# NANO103.net
KiCad netlist of a schematic drawn in Altium Designer
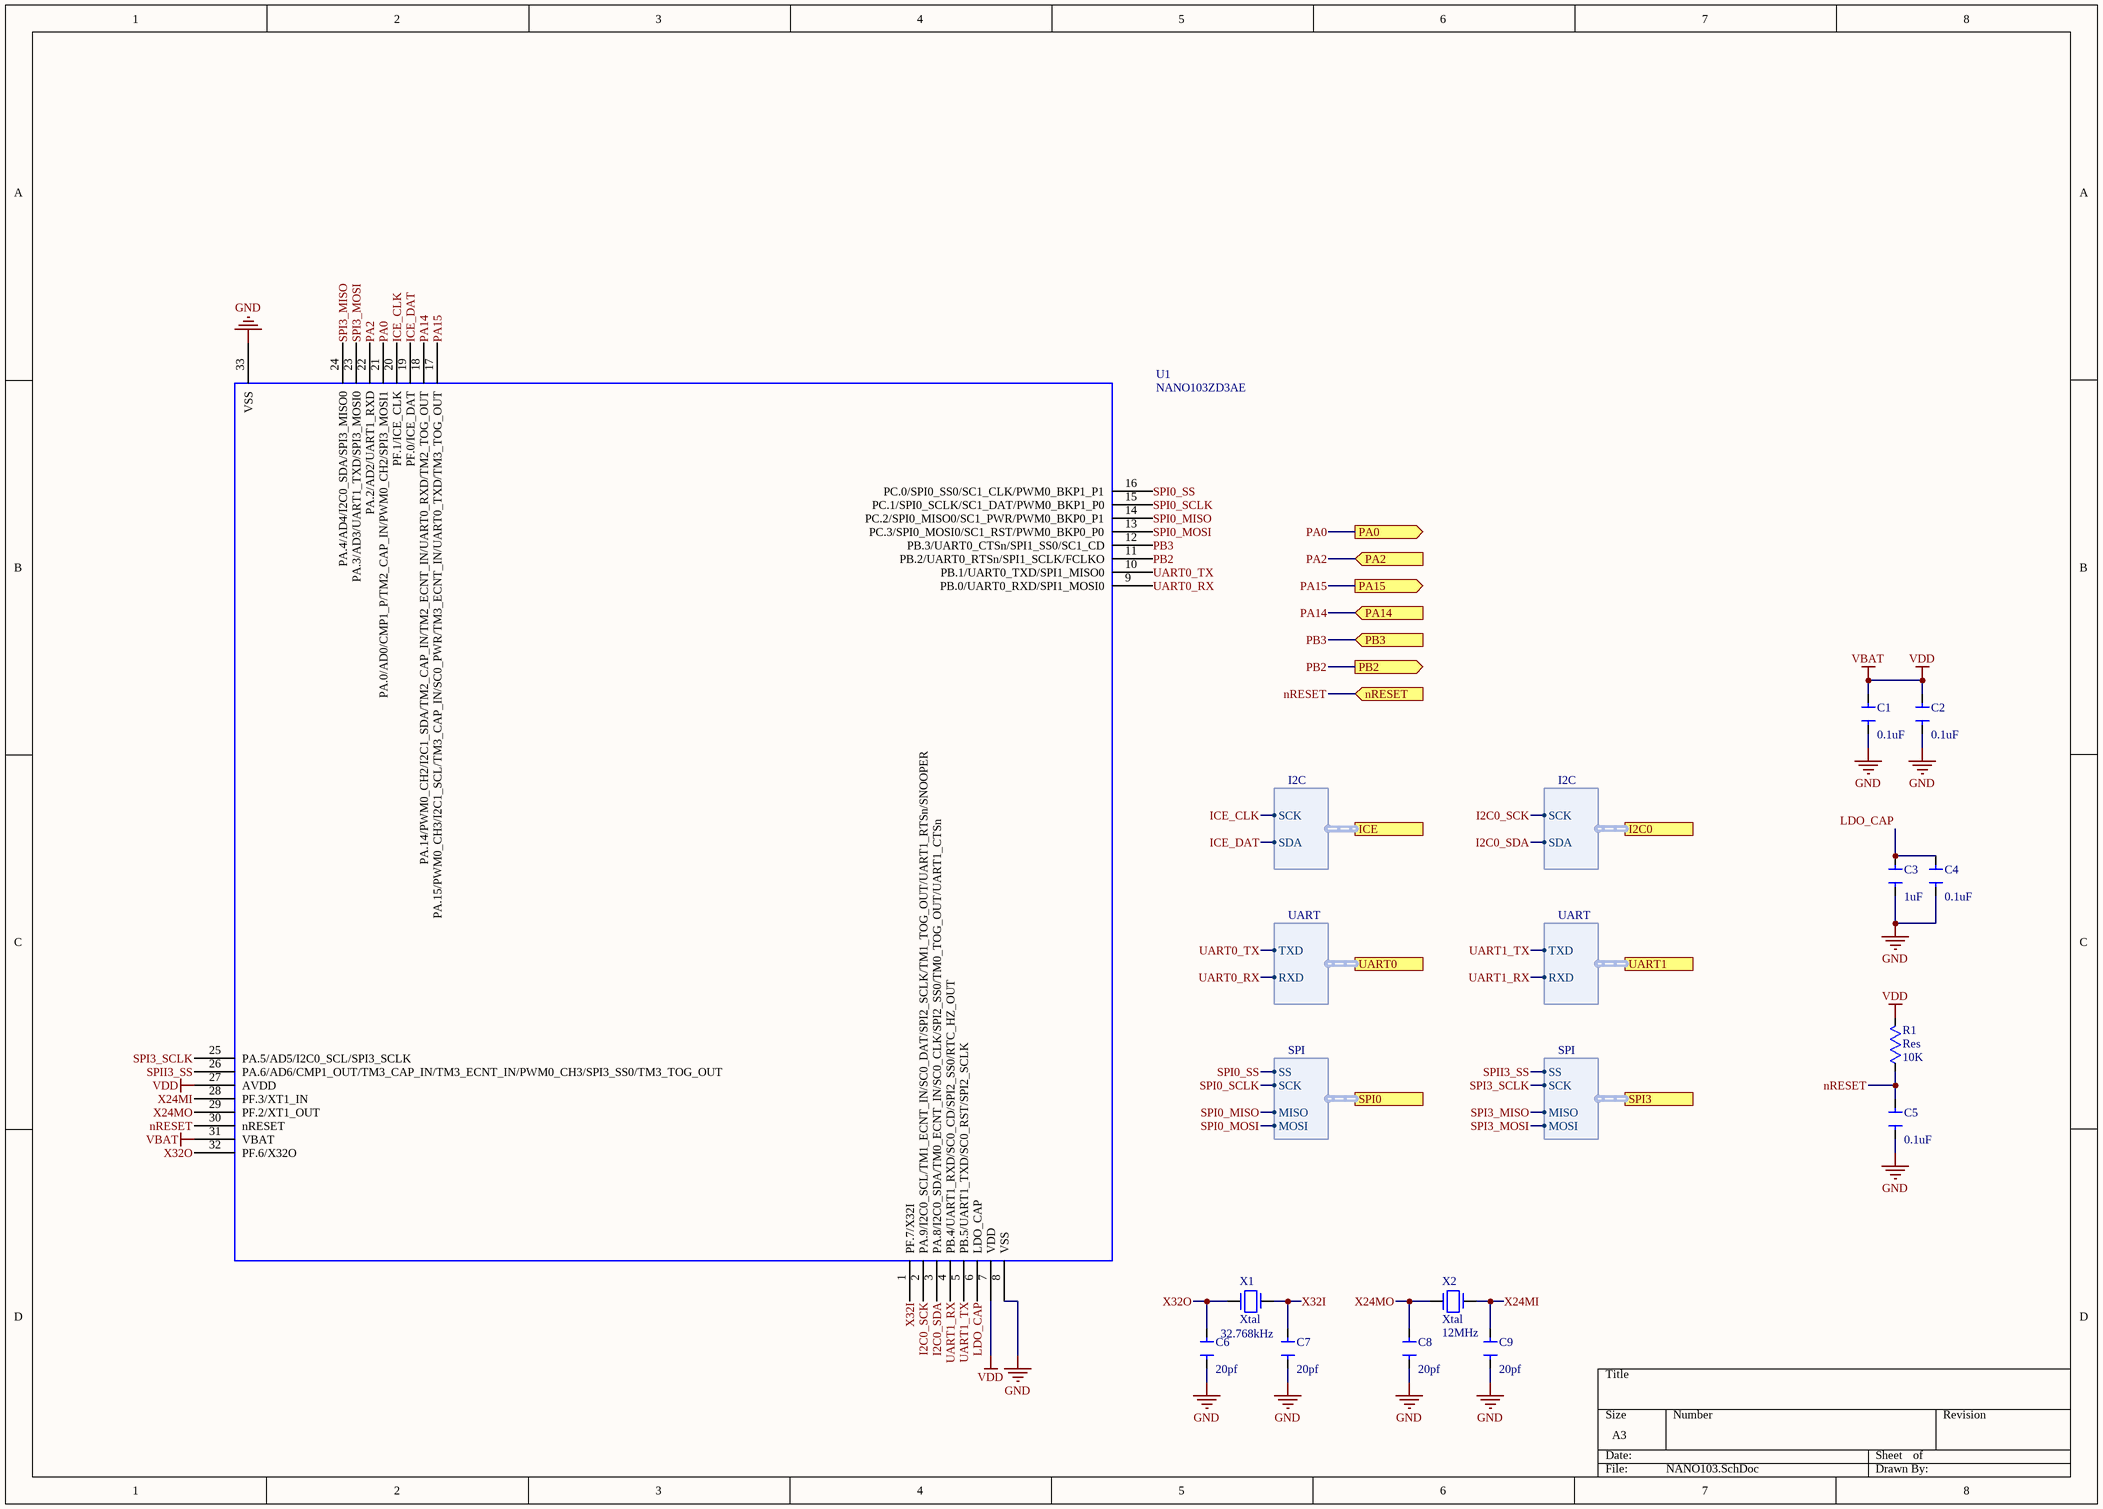
[diagram p0: NANO103.SchDoc]

(export (version "E")
  (design (tool "Eeschema 10.0.6"))
  (components
    (comp (ref "C1")
      (value "0.1uF")
      (footprint "Cap_0603")
      (fields (field (name "Comment") "Cap"))
      (libsource (lib "ZGR") (part "Cap"))
    )
    (comp (ref "C2")
      (value "0.1uF")
      (footprint "Cap_0603")
      (fields (field (name "Comment") "Cap"))
      (libsource (lib "ZGR") (part "Cap"))
    )
    (comp (ref "C3")
      (value "1uF")
      (footprint "Cap_0603")
      (fields (field (name "Comment") "Cap"))
      (libsource (lib "ZGR") (part "Cap"))
    )
    (comp (ref "C4")
      (value "0.1uF")
      (footprint "Cap_0603")
      (fields (field (name "Comment") "Cap"))
      (libsource (lib "ZGR") (part "Cap"))
    )
    (comp (ref "C5")
      (value "0.1uF")
      (footprint "Cap_0603")
      (fields (field (name "Comment") "Cap"))
      (libsource (lib "ZGR") (part "Cap"))
    )
    (comp (ref "C6")
      (value "20pf")
      (footprint "Cap_0603")
      (fields (field (name "Comment") "Cap"))
      (libsource (lib "ZGR") (part "Cap"))
    )
    (comp (ref "C7")
      (value "20pf")
      (footprint "Cap_0603")
      (fields (field (name "Comment") "Cap"))
      (libsource (lib "ZGR") (part "Cap"))
    )
    (comp (ref "C8")
      (value "20pf")
      (footprint "Cap_0603")
      (fields (field (name "Comment") "Cap"))
      (libsource (lib "ZGR") (part "Cap"))
    )
    (comp (ref "C9")
      (value "20pf")
      (footprint "Cap_0603")
      (fields (field (name "Comment") "Cap"))
      (libsource (lib "ZGR") (part "Cap"))
    )
    (comp (ref "R1")
      (value "Res")
      (footprint "RES_0603")
      (fields (field (name "ALTIUM_VALUE") "10K"))
      (libsource (lib "ZGR") (part "Res"))
    )
    (comp (ref "U1")
      (value "NANO103ZD3AE")
      (footprint "MCU_QFN_33_5x5")
      (libsource (lib "NUVOTON") (part "NANO103ZD3AE"))
    )
    (comp (ref "X1")
      (value "Xtal")
      (footprint "X3215")
      (fields (field (name "ALTIUM_VALUE") "32.768kHz"))
      (libsource (lib "ZGR") (part "Xtal"))
    )
    (comp (ref "X2")
      (value "Xtal")
      (footprint "2520S")
      (fields (field (name "ALTIUM_VALUE") "12MHz"))
      (libsource (lib "ZGR") (part "Xtal"))
    )
  )
  (nets
    (net (code "4") (name "/I2C0_SCK") (class "Default")
      (node (ref "U1") (pin "2") (pinfunction "PA.9/I2C0_SCL/TM1_ECNT_IN/SC0_DAT/SPI2_SCLK/TM1_TOG_OUT/UART1_RTSn/SNOOPER_2") (pintype "passive"))
    )
    (net (code "5") (name "/I2C0_SDA") (class "Default")
      (node (ref "U1") (pin "3") (pinfunction "PA.8/I2C0_SDA/TM0_ECNT_IN/SC0_CLK/SPI2_SS0/TM0_TOG_OUT/UART1_CTSn_3") (pintype "passive"))
    )
    (net (code "6") (name "/ICE_CLK") (class "Default")
      (node (ref "U1") (pin "20") (pinfunction "PF.1/ICE_CLK_20") (pintype "passive"))
    )
    (net (code "7") (name "/ICE_DAT") (class "Default")
      (node (ref "U1") (pin "19") (pinfunction "PF.0/ICE_DAT_19") (pintype "passive"))
    )
    (net (code "8") (name "/LDO_CAP") (class "Default")
      (node (ref "C3") (pin "1") (pinfunction "1_1") (pintype "passive"))
      (node (ref "C4") (pin "1") (pinfunction "1_1") (pintype "passive"))
      (node (ref "U1") (pin "6") (pinfunction "LDO_CAP_6") (pintype "passive"))
    )
    (net (code "9") (name "/PA0") (class "Default")
      (node (ref "U1") (pin "21") (pinfunction "PA.0/AD0/CMP1_P/TM2_CAP_IN/PWM0_CH2/SPI3_MOSI1_21") (pintype "passive"))
    )
    (net (code "10") (name "/PA2") (class "Default")
      (node (ref "U1") (pin "22") (pinfunction "PA.2/AD2/UART1_RXD_22") (pintype "passive"))
    )
    (net (code "11") (name "/PA14") (class "Default")
      (node (ref "U1") (pin "18") (pinfunction "PA.14/PWM0_CH2/I2C1_SDA/TM2_CAP_IN/TM2_ECNT_IN/UART0_RXD/TM2_TOG_OUT_18") (pintype "passive"))
    )
    (net (code "12") (name "/PA15") (class "Default")
      (node (ref "U1") (pin "17") (pinfunction "PA.15/PWM0_CH3/I2C1_SCL/TM3_CAP_IN/SC0_PWR/TM3_ECNT_IN/UART0_TXD/TM3_TOG_OUT_17") (pintype "passive"))
    )
    (net (code "13") (name "/PB2") (class "Default")
      (node (ref "U1") (pin "11") (pinfunction "PB.2/UART0_RTSn/SPI1_SCLK/FCLKO_11") (pintype "passive"))
    )
    (net (code "14") (name "/PB3") (class "Default")
      (node (ref "U1") (pin "12") (pinfunction "PB.3/UART0_CTSn/SPI1_SS0/SC1_CD_12") (pintype "passive"))
    )
    (net (code "15") (name "/SPI0_MISO") (class "Default")
      (node (ref "U1") (pin "14") (pinfunction "PC.2/SPI0_MISO0/SC1_PWR/PWM0_BKP0_P1_14") (pintype "passive"))
    )
    (net (code "16") (name "/SPI0_MOSI") (class "Default")
      (node (ref "U1") (pin "13") (pinfunction "PC.3/SPI0_MOSI0/SC1_RST/PWM0_BKP0_P0_13") (pintype "passive"))
    )
    (net (code "17") (name "/SPI0_SCLK") (class "Default")
      (node (ref "U1") (pin "15") (pinfunction "PC.1/SPI0_SCLK/SC1_DAT/PWM0_BKP1_P0_15") (pintype "passive"))
    )
    (net (code "18") (name "/SPI0_SS") (class "Default")
      (node (ref "U1") (pin "16") (pinfunction "PC.0/SPI0_SS0/SC1_CLK/PWM0_BKP1_P1_16") (pintype "passive"))
    )
    (net (code "19") (name "/SPI3_MISO") (class "Default")
      (node (ref "U1") (pin "24") (pinfunction "PA.4/AD4/I2C0_SDA/SPI3_MISO0_24") (pintype "passive"))
    )
    (net (code "20") (name "/SPI3_MOSI") (class "Default")
      (node (ref "U1") (pin "23") (pinfunction "PA.3/AD3/UART1_TXD/SPI3_MOSI0_23") (pintype "passive"))
    )
    (net (code "21") (name "/SPI3_SCLK") (class "Default")
      (node (ref "U1") (pin "25") (pinfunction "PA.5/AD5/I2C0_SCL/SPI3_SCLK_25") (pintype "passive"))
    )
    (net (code "22") (name "/SPII3_SS") (class "Default")
      (node (ref "U1") (pin "26") (pinfunction "PA.6/AD6/CMP1_OUT/TM3_CAP_IN/TM3_ECNT_IN/PWM0_CH3/SPI3_SS0/TM3_TOG_OUT_26") (pintype "passive"))
    )
    (net (code "23") (name "/UART0_RX") (class "Default")
      (node (ref "U1") (pin "9") (pinfunction "PB.0/UART0_RXD/SPI1_MOSI0_9") (pintype "passive"))
    )
    (net (code "24") (name "/UART0_TX") (class "Default")
      (node (ref "U1") (pin "10") (pinfunction "PB.1/UART0_TXD/SPI1_MISO0_10") (pintype "passive"))
    )
    (net (code "25") (name "/UART1_RX") (class "Default")
      (node (ref "U1") (pin "4") (pinfunction "PB.4/UART1_RXD/SC0_CD/SPI2_SS0/RTC_HZ_OUT_4") (pintype "passive"))
    )
    (net (code "26") (name "/UART1_TX") (class "Default")
      (node (ref "U1") (pin "5") (pinfunction "PB.5/UART1_TXD/SC0_RST/SPI2_SCLK_5") (pintype "passive"))
    )
    (net (code "27") (name "/X24MI") (class "Default")
      (node (ref "C9") (pin "1") (pinfunction "1_1") (pintype "passive"))
      (node (ref "U1") (pin "28") (pinfunction "PF.3/XT1_IN_28") (pintype "passive"))
      (node (ref "X2") (pin "1") (pintype "passive"))
    )
    (net (code "28") (name "/X24MO") (class "Default")
      (node (ref "C8") (pin "1") (pinfunction "1_1") (pintype "passive"))
      (node (ref "U1") (pin "29") (pinfunction "PF.2/XT1_OUT_29") (pintype "passive"))
      (node (ref "X2") (pin "2") (pintype "passive"))
    )
    (net (code "29") (name "/X32I") (class "Default")
      (node (ref "C7") (pin "1") (pinfunction "1_1") (pintype "passive"))
      (node (ref "U1") (pin "1") (pinfunction "PF.7/X32I_1") (pintype "passive"))
      (node (ref "X1") (pin "1") (pintype "passive"))
    )
    (net (code "30") (name "/X32O") (class "Default")
      (node (ref "C6") (pin "1") (pinfunction "1_1") (pintype "passive"))
      (node (ref "U1") (pin "32") (pinfunction "PF.6/X32O_32") (pintype "passive"))
      (node (ref "X1") (pin "2") (pintype "passive"))
    )
    (net (code "31") (name "/nRESET") (class "Default")
      (node (ref "C5") (pin "1") (pinfunction "1_1") (pintype "passive"))
      (node (ref "R1") (pin "2") (pinfunction "2_2") (pintype "passive"))
      (node (ref "U1") (pin "30") (pinfunction "nRESET_30") (pintype "passive"))
    )
    (net (code "35") (name "GND") (class "Default")
      (node (ref "C1") (pin "2") (pinfunction "2_2") (pintype "passive"))
      (node (ref "C2") (pin "2") (pinfunction "2_2") (pintype "passive"))
      (node (ref "C3") (pin "2") (pinfunction "2_2") (pintype "passive"))
      (node (ref "C4") (pin "2") (pinfunction "2_2") (pintype "passive"))
      (node (ref "C5") (pin "2") (pinfunction "2_2") (pintype "passive"))
      (node (ref "C6") (pin "2") (pinfunction "2_2") (pintype "passive"))
      (node (ref "C7") (pin "2") (pinfunction "2_2") (pintype "passive"))
      (node (ref "C8") (pin "2") (pinfunction "2_2") (pintype "passive"))
      (node (ref "C9") (pin "2") (pinfunction "2_2") (pintype "passive"))
      (node (ref "U1") (pin "33") (pinfunction "VSS_33") (pintype "passive"))
      (node (ref "U1") (pin "8") (pinfunction "VSS_8") (pintype "passive"))
    )
    (net (code "36") (name "VBAT") (class "Default")
      (node (ref "C1") (pin "1") (pinfunction "1_1") (pintype "passive"))
      (node (ref "C2") (pin "1") (pinfunction "1_1") (pintype "passive"))
      (node (ref "R1") (pin "1") (pinfunction "1_1") (pintype "passive"))
      (node (ref "U1") (pin "27") (pinfunction "AVDD_27") (pintype "passive"))
      (node (ref "U1") (pin "31") (pinfunction "VBAT_31") (pintype "passive"))
      (node (ref "U1") (pin "7") (pinfunction "VDD_7") (pintype "passive"))
    )
  )
)
